# board_c-01.net
KiCad netlist of a schematic drawn in EAGLE
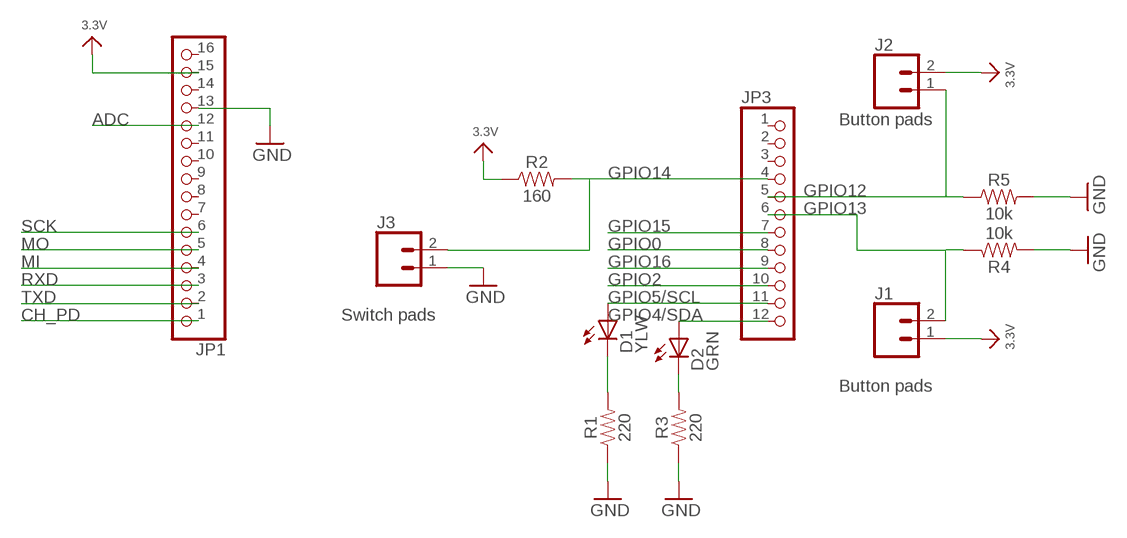
[diagram p0: schematic, sheet 1]

(export (version "E")
  (design (tool "Eeschema 10.0.6"))
  (components
    (comp (ref "D1")
      (value "YLW")
      (footprint "eagle-import:LED3MM")
      (libsource (lib "eagle-import") (part "LED3MM"))
    )
    (comp (ref "D2")
      (value "GRN")
      (footprint "eagle-import:LED3MM")
      (libsource (lib "eagle-import") (part "LED3MM"))
    )
    (comp (ref "J1")
      (value "CONN_02LOCK_LONGPADS")
      (footprint "eagle-import:1X02_LOCK_LONGPADS")
      (libsource (lib "eagle-import") (part "CONN_02LOCK_LONGPADS"))
    )
    (comp (ref "J2")
      (value "CONN_02LOCK_LONGPADS")
      (footprint "eagle-import:1X02_LOCK_LONGPADS")
      (libsource (lib "eagle-import") (part "CONN_02LOCK_LONGPADS"))
    )
    (comp (ref "J3")
      (value "CONN_02LOCK_LONGPADS")
      (footprint "eagle-import:1X02_LOCK_LONGPADS")
      (libsource (lib "eagle-import") (part "CONN_02LOCK_LONGPADS"))
    )
    (comp (ref "JP1")
      (value "HEADER-1X16ROUND")
      (footprint "eagle-import:1X16_ROUND")
      (libsource (lib "eagle-import") (part "HEADER-1X16ROUND"))
    )
    (comp (ref "JP3")
      (value "HEADER-1X12")
      (footprint "eagle-import:1X12_ROUND")
      (libsource (lib "eagle-import") (part "HEADER-1X12"))
    )
    (comp (ref "R1")
      (value "220")
      (footprint "eagle-import:AXIAL-0.3")
      (libsource (lib "eagle-import") (part "1KOHM-HORIZ-1/4W-1%"))
    )
    (comp (ref "R2")
      (value "160")
      (footprint "eagle-import:AXIAL-0.3")
      (libsource (lib "eagle-import") (part "1KOHM-HORIZ-1/4W-1%"))
    )
    (comp (ref "R3")
      (value "220")
      (footprint "eagle-import:AXIAL-0.3")
      (libsource (lib "eagle-import") (part "1KOHM-HORIZ-1/4W-1%"))
    )
    (comp (ref "R4")
      (value "10k")
      (footprint "eagle-import:AXIAL-0.3")
      (libsource (lib "eagle-import") (part "1KOHM-HORIZ-1/4W-1%"))
    )
    (comp (ref "R5")
      (value "10k")
      (footprint "eagle-import:AXIAL-0.3")
      (libsource (lib "eagle-import") (part "1KOHM-HORIZ-1/4W-1%"))
    )
  )
  (nets
    (net (code "1") (name "/ADC") (class "Default")
      (node (ref "JP1") (pin "12") (pinfunction "12_12") (pintype "passive"))
    )
    (net (code "2") (name "/CH_PD") (class "Default")
      (node (ref "JP1") (pin "1") (pinfunction "1_1") (pintype "passive"))
    )
    (net (code "3") (name "/GPIO0") (class "Default")
      (node (ref "JP3") (pin "8") (pinfunction "8_8") (pintype "passive"))
    )
    (net (code "4") (name "/GPIO2") (class "Default")
      (node (ref "JP3") (pin "10") (pinfunction "10_10") (pintype "passive"))
    )
    (net (code "5") (name "/GPIO4{slash}SDA") (class "Default")
      (node (ref "D2") (pin "A") (pinfunction "A_A") (pintype "passive"))
      (node (ref "JP3") (pin "12") (pinfunction "12_12") (pintype "passive"))
    )
    (net (code "6") (name "/GPIO5{slash}SCL") (class "Default")
      (node (ref "D1") (pin "A") (pinfunction "A_A") (pintype "passive"))
      (node (ref "JP3") (pin "11") (pinfunction "11_11") (pintype "passive"))
    )
    (net (code "7") (name "/GPIO12") (class "Default")
      (node (ref "J2") (pin "1") (pinfunction "1_1") (pintype "passive"))
      (node (ref "JP3") (pin "5") (pinfunction "5_5") (pintype "passive"))
      (node (ref "R5") (pin "P$1") (pinfunction "1_P$1") (pintype "passive"))
    )
    (net (code "8") (name "/GPIO13") (class "Default")
      (node (ref "J1") (pin "2") (pinfunction "2_2") (pintype "passive"))
      (node (ref "JP3") (pin "6") (pinfunction "6_6") (pintype "passive"))
      (node (ref "R4") (pin "P$1") (pinfunction "1_P$1") (pintype "passive"))
    )
    (net (code "9") (name "/GPIO14") (class "Default")
      (node (ref "J3") (pin "2") (pinfunction "2_2") (pintype "passive"))
      (node (ref "JP3") (pin "4") (pinfunction "4_4") (pintype "passive"))
      (node (ref "R2") (pin "P$2") (pinfunction "2_P$2") (pintype "passive"))
    )
    (net (code "10") (name "/GPIO15") (class "Default")
      (node (ref "JP3") (pin "7") (pinfunction "7_7") (pintype "passive"))
    )
    (net (code "11") (name "/GPIO16") (class "Default")
      (node (ref "JP3") (pin "9") (pinfunction "9_9") (pintype "passive"))
    )
    (net (code "12") (name "/MI") (class "Default")
      (node (ref "JP1") (pin "4") (pinfunction "4_4") (pintype "passive"))
    )
    (net (code "13") (name "/MO") (class "Default")
      (node (ref "JP1") (pin "5") (pinfunction "5_5") (pintype "passive"))
    )
    (net (code "14") (name "/RXD") (class "Default")
      (node (ref "JP1") (pin "3") (pinfunction "3_3") (pintype "passive"))
    )
    (net (code "15") (name "/SCK") (class "Default")
      (node (ref "JP1") (pin "6") (pinfunction "6_6") (pintype "passive"))
    )
    (net (code "16") (name "/TXD") (class "Default")
      (node (ref "JP1") (pin "2") (pinfunction "2_2") (pintype "passive"))
    )
    (net (code "17") (name "3.3V") (class "Default")
      (node (ref "J1") (pin "1") (pinfunction "1_1") (pintype "passive"))
      (node (ref "J2") (pin "2") (pinfunction "2_2") (pintype "passive"))
      (node (ref "JP1") (pin "15") (pinfunction "15_15") (pintype "passive"))
      (node (ref "R2") (pin "P$1") (pinfunction "1_P$1") (pintype "passive"))
    )
    (net (code "18") (name "GND") (class "Default")
      (node (ref "J3") (pin "1") (pinfunction "1_1") (pintype "passive"))
      (node (ref "JP1") (pin "13") (pinfunction "13_13") (pintype "passive"))
      (node (ref "R1") (pin "P$1") (pinfunction "1_P$1") (pintype "passive"))
      (node (ref "R3") (pin "P$1") (pinfunction "1_P$1") (pintype "passive"))
      (node (ref "R4") (pin "P$2") (pinfunction "2_P$2") (pintype "passive"))
      (node (ref "R5") (pin "P$2") (pinfunction "2_P$2") (pintype "passive"))
    )
    (net (code "19") (name "Net-(D1-C)") (class "Default")
      (node (ref "D1") (pin "K") (pinfunction "C_K") (pintype "passive"))
      (node (ref "R1") (pin "P$2") (pinfunction "2_P$2") (pintype "passive"))
    )
    (net (code "20") (name "Net-(D2-C)") (class "Default")
      (node (ref "D2") (pin "K") (pinfunction "C_K") (pintype "passive"))
      (node (ref "R3") (pin "P$2") (pinfunction "2_P$2") (pintype "passive"))
    )
    (net (code "21") (name "unconnected-(JP1-Pad7)") (class "Default")
      (node (ref "JP1") (pin "7") (pinfunction "7_7") (pintype "passive"))
    )
    (net (code "22") (name "unconnected-(JP1-Pad8)") (class "Default")
      (node (ref "JP1") (pin "8") (pinfunction "8_8") (pintype "passive"))
    )
    (net (code "23") (name "unconnected-(JP1-Pad9)") (class "Default")
      (node (ref "JP1") (pin "9") (pinfunction "9_9") (pintype "passive"))
    )
    (net (code "24") (name "unconnected-(JP1-Pad10)") (class "Default")
      (node (ref "JP1") (pin "10") (pinfunction "10_10") (pintype "passive"))
    )
    (net (code "25") (name "unconnected-(JP1-Pad11)") (class "Default")
      (node (ref "JP1") (pin "11") (pinfunction "11_11") (pintype "passive"))
    )
    (net (code "26") (name "unconnected-(JP1-Pad14)") (class "Default")
      (node (ref "JP1") (pin "14") (pinfunction "14_14") (pintype "passive"))
    )
    (net (code "27") (name "unconnected-(JP1-Pad16)") (class "Default")
      (node (ref "JP1") (pin "16") (pinfunction "16_16") (pintype "passive"))
    )
    (net (code "28") (name "unconnected-(JP3-Pad1)") (class "Default")
      (node (ref "JP3") (pin "1") (pinfunction "1_1") (pintype "passive"))
    )
    (net (code "29") (name "unconnected-(JP3-Pad2)") (class "Default")
      (node (ref "JP3") (pin "2") (pinfunction "2_2") (pintype "passive"))
    )
    (net (code "30") (name "unconnected-(JP3-Pad3)") (class "Default")
      (node (ref "JP3") (pin "3") (pinfunction "3_3") (pintype "passive"))
    )
  )
)
